# Lightbox.net
KiCad netlist of a schematic drawn in EAGLE
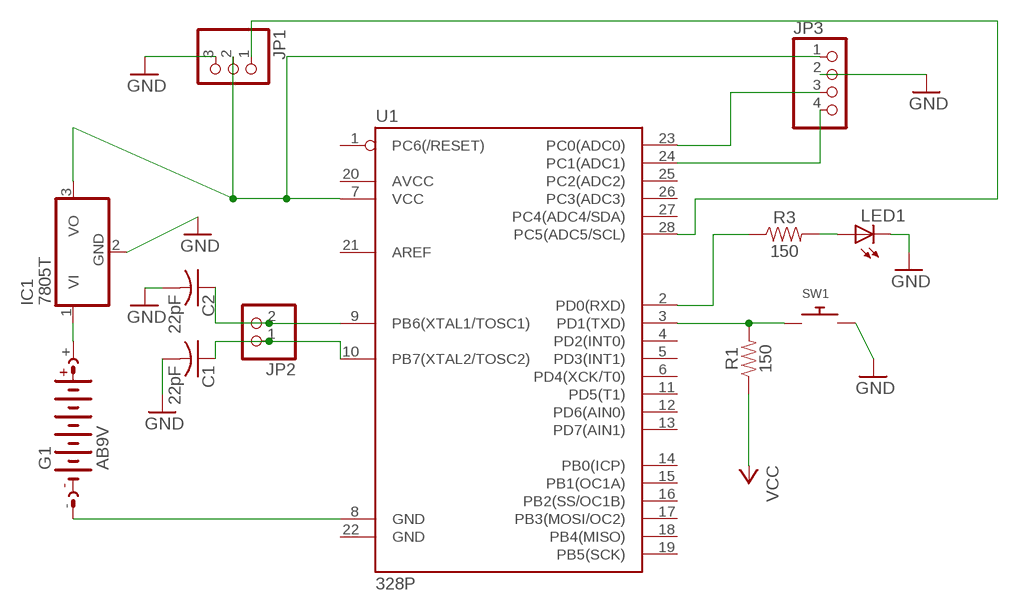
[diagram p0: schematic, sheet 1]

(export (version "E")
  (design (tool "Eeschema 10.0.6"))
  (components
    (comp (ref "C1")
      (value "22pF")
      (footprint "eagle-import:C025-024X044")
      (libsource (lib "eagle-import") (part "C-US025-024X044"))
    )
    (comp (ref "C2")
      (value "22pF")
      (footprint "eagle-import:C025-024X044")
      (libsource (lib "eagle-import") (part "C-US025-024X044"))
    )
    (comp (ref "G1")
      (value "AB9V")
      (footprint "eagle-import:AB9V")
      (libsource (lib "eagle-import") (part "AB9V"))
    )
    (comp (ref "IC1")
      (value "7805T")
      (footprint "eagle-import:TO220H")
      (libsource (lib "eagle-import") (part "78T05"))
    )
    (comp (ref "JP1")
      (value "PINHD-1X3")
      (footprint "eagle-import:1X03")
      (libsource (lib "eagle-import") (part "PINHD-1X3"))
    )
    (comp (ref "JP2")
      (value "PINHD-1X2")
      (footprint "eagle-import:1X02")
      (libsource (lib "eagle-import") (part "PINHD-1X2"))
    )
    (comp (ref "JP3")
      (value "PINHD-1X4")
      (footprint "eagle-import:1X04")
      (libsource (lib "eagle-import") (part "PINHD-1X4"))
    )
    (comp (ref "LED1")
      (value "LED5MM")
      (footprint "eagle-import:LED5MM")
      (libsource (lib "eagle-import") (part "LED5MM"))
    )
    (comp (ref "R1")
      (value "150")
      (footprint "eagle-import:0603")
      (libsource (lib "eagle-import") (part "150OHM-0603-1/10W-1%"))
    )
    (comp (ref "R3")
      (value "150")
      (footprint "eagle-import:0603")
      (libsource (lib "eagle-import") (part "150OHM-0603-1/10W-1%"))
    )
    (comp (ref "SW1")
      (value "SWITCH_PUSHBUTTONEVQ-PE")
      (footprint "eagle-import:TACT_PANA-EVQ")
      (libsource (lib "eagle-import") (part "SWITCH_PUSHBUTTONEVQ-PE"))
    )
    (comp (ref "U1")
      (value "328P")
      (footprint "eagle-import:DIP28")
      (libsource (lib "eagle-import") (part "ATMEGA328P_PDIP"))
    )
  )
  (nets
    (net (code "1") (name "GND") (class "Default")
      (node (ref "C1") (pin "2") (pinfunction "2_2") (pintype "passive"))
      (node (ref "C2") (pin "2") (pinfunction "2_2") (pintype "passive"))
      (node (ref "IC1") (pin "2") (pinfunction "GND_2") (pintype "passive"))
      (node (ref "JP1") (pin "3") (pinfunction "3_3") (pintype "passive"))
      (node (ref "JP3") (pin "2") (pinfunction "2_2") (pintype "passive"))
      (node (ref "LED1") (pin "K") (pinfunction "C_K") (pintype "passive"))
      (node (ref "SW1") (pin "P$2") (pinfunction "P$2_P$2") (pintype "passive"))
    )
    (net (code "2") (name "Net-(G1-Pad-)") (class "Default")
      (node (ref "G1") (pin "-") (pinfunction "-_-") (pintype "passive"))
      (node (ref "U1") (pin "8") (pinfunction "GND_8") (pintype "bidirectional"))
    )
    (net (code "3") (name "Net-(IC1-VI)") (class "Default")
      (node (ref "G1") (pin "+") (pinfunction "+_+") (pintype "passive"))
      (node (ref "IC1") (pin "1") (pinfunction "VI_1") (pintype "input"))
    )
    (net (code "4") (name "Net-(IC1-VO)") (class "Default")
      (node (ref "IC1") (pin "3") (pinfunction "VO_3") (pintype "passive"))
      (node (ref "JP1") (pin "2") (pinfunction "2_2") (pintype "passive"))
      (node (ref "JP3") (pin "1") (pinfunction "1_1") (pintype "passive"))
      (node (ref "U1") (pin "7") (pinfunction "VCC_7") (pintype "bidirectional"))
    )
    (net (code "5") (name "Net-(LED1-PadA)") (class "Default")
      (node (ref "LED1") (pin "A") (pinfunction "A_A") (pintype "passive"))
      (node (ref "R3") (pin "2") (pinfunction "2_2") (pintype "passive"))
    )
    (net (code "6") (name "Net-(U1-PB6(XTAL1{slash}TOSC1))") (class "Default")
      (node (ref "C2") (pin "1") (pinfunction "1_1") (pintype "passive"))
      (node (ref "JP2") (pin "2") (pinfunction "2_2") (pintype "passive"))
      (node (ref "U1") (pin "9") (pinfunction "PB6(XTAL1/TOSC1)_9") (pintype "bidirectional"))
    )
    (net (code "7") (name "Net-(U1-PB7(XTAL2{slash}TOSC2))") (class "Default")
      (node (ref "C1") (pin "1") (pinfunction "1_1") (pintype "passive"))
      (node (ref "JP2") (pin "1") (pinfunction "1_1") (pintype "passive"))
      (node (ref "U1") (pin "10") (pinfunction "PB7(XTAL2/TOSC2)_10") (pintype "bidirectional"))
    )
    (net (code "8") (name "Net-(U1-PC0(ADC0))") (class "Default")
      (node (ref "JP3") (pin "3") (pinfunction "3_3") (pintype "passive"))
      (node (ref "U1") (pin "23") (pinfunction "PC0(ADC0)_23") (pintype "bidirectional"))
    )
    (net (code "9") (name "Net-(U1-PC1(ADC1))") (class "Default")
      (node (ref "JP3") (pin "4") (pinfunction "4_4") (pintype "passive"))
      (node (ref "U1") (pin "24") (pinfunction "PC1(ADC1)_24") (pintype "bidirectional"))
    )
    (net (code "10") (name "Net-(U1-PC5(ADC5{slash}SCL))") (class "Default")
      (node (ref "JP1") (pin "1") (pinfunction "1_1") (pintype "passive"))
      (node (ref "U1") (pin "28") (pinfunction "PC5(ADC5/SCL)_28") (pintype "bidirectional"))
    )
    (net (code "11") (name "Net-(U1-PD0(RXD))") (class "Default")
      (node (ref "R3") (pin "1") (pinfunction "1_1") (pintype "passive"))
      (node (ref "U1") (pin "2") (pinfunction "PD0(RXD)_2") (pintype "bidirectional"))
    )
    (net (code "12") (name "Net-(U1-PD1(TXD))") (class "Default")
      (node (ref "R1") (pin "2") (pinfunction "2_2") (pintype "passive"))
      (node (ref "SW1") (pin "P$1") (pinfunction "P$1_P$1") (pintype "passive"))
      (node (ref "U1") (pin "3") (pinfunction "PD1(TXD)_3") (pintype "bidirectional"))
    )
    (net (code "13") (name "VCC") (class "Default")
      (node (ref "R1") (pin "1") (pinfunction "1_1") (pintype "passive"))
    )
    (net (code "14") (name "unconnected-(U1-AREF-Pad21)") (class "Default")
      (node (ref "U1") (pin "21") (pinfunction "AREF_21") (pintype "bidirectional"))
    )
    (net (code "15") (name "unconnected-(U1-AVCC-Pad20)") (class "Default")
      (node (ref "U1") (pin "20") (pinfunction "AVCC_20") (pintype "bidirectional"))
    )
    (net (code "16") (name "unconnected-(U1-GND-Pad22)") (class "Default")
      (node (ref "U1") (pin "22") (pinfunction "GND_22") (pintype "bidirectional"))
    )
    (net (code "17") (name "unconnected-(U1-PB0(ICP)-Pad14)") (class "Default")
      (node (ref "U1") (pin "14") (pinfunction "PB0(ICP)_14") (pintype "bidirectional"))
    )
    (net (code "18") (name "unconnected-(U1-PB1(OC1A)-Pad15)") (class "Default")
      (node (ref "U1") (pin "15") (pinfunction "PB1(OC1A)_15") (pintype "bidirectional"))
    )
    (net (code "19") (name "unconnected-(U1-PB2(SS{slash}OC1B)-Pad16)") (class "Default")
      (node (ref "U1") (pin "16") (pinfunction "PB2(SS/OC1B)_16") (pintype "bidirectional"))
    )
    (net (code "20") (name "unconnected-(U1-PB3(MOSI{slash}OC2)-Pad17)") (class "Default")
      (node (ref "U1") (pin "17") (pinfunction "PB3(MOSI/OC2)_17") (pintype "bidirectional"))
    )
    (net (code "21") (name "unconnected-(U1-PB4(MISO)-Pad18)") (class "Default")
      (node (ref "U1") (pin "18") (pinfunction "PB4(MISO)_18") (pintype "bidirectional"))
    )
    (net (code "22") (name "unconnected-(U1-PB5(SCK)-Pad19)") (class "Default")
      (node (ref "U1") (pin "19") (pinfunction "PB5(SCK)_19") (pintype "bidirectional"))
    )
    (net (code "23") (name "unconnected-(U1-PC2(ADC2)-Pad25)") (class "Default")
      (node (ref "U1") (pin "25") (pinfunction "PC2(ADC2)_25") (pintype "bidirectional"))
    )
    (net (code "24") (name "unconnected-(U1-PC3(ADC3)-Pad26)") (class "Default")
      (node (ref "U1") (pin "26") (pinfunction "PC3(ADC3)_26") (pintype "bidirectional"))
    )
    (net (code "25") (name "unconnected-(U1-PC4(ADC4{slash}SDA)-Pad27)") (class "Default")
      (node (ref "U1") (pin "27") (pinfunction "PC4(ADC4/SDA)_27") (pintype "bidirectional"))
    )
    (net (code "26") (name "unconnected-(U1-PC6({slash}RESET)-Pad1)") (class "Default")
      (node (ref "U1") (pin "1") (pinfunction "PC6(/RESET)_1") (pintype "bidirectional"))
    )
    (net (code "27") (name "unconnected-(U1-PD2(INT0)-Pad4)") (class "Default")
      (node (ref "U1") (pin "4") (pinfunction "PD2(INT0)_4") (pintype "bidirectional"))
    )
    (net (code "28") (name "unconnected-(U1-PD3(INT1)-Pad5)") (class "Default")
      (node (ref "U1") (pin "5") (pinfunction "PD3(INT1)_5") (pintype "bidirectional"))
    )
    (net (code "29") (name "unconnected-(U1-PD4(XCK{slash}T0)-Pad6)") (class "Default")
      (node (ref "U1") (pin "6") (pinfunction "PD4(XCK/T0)_6") (pintype "bidirectional"))
    )
    (net (code "30") (name "unconnected-(U1-PD5(T1)-Pad11)") (class "Default")
      (node (ref "U1") (pin "11") (pinfunction "PD5(T1)_11") (pintype "bidirectional"))
    )
    (net (code "31") (name "unconnected-(U1-PD6(AIN0)-Pad12)") (class "Default")
      (node (ref "U1") (pin "12") (pinfunction "PD6(AIN0)_12") (pintype "bidirectional"))
    )
    (net (code "32") (name "unconnected-(U1-PD7(AIN1)-Pad13)") (class "Default")
      (node (ref "U1") (pin "13") (pinfunction "PD7(AIN1)_13") (pintype "bidirectional"))
    )
  )
)
